# RPI-Lora-Gateway-Shield.net
KiCad netlist of a schematic drawn in EAGLE
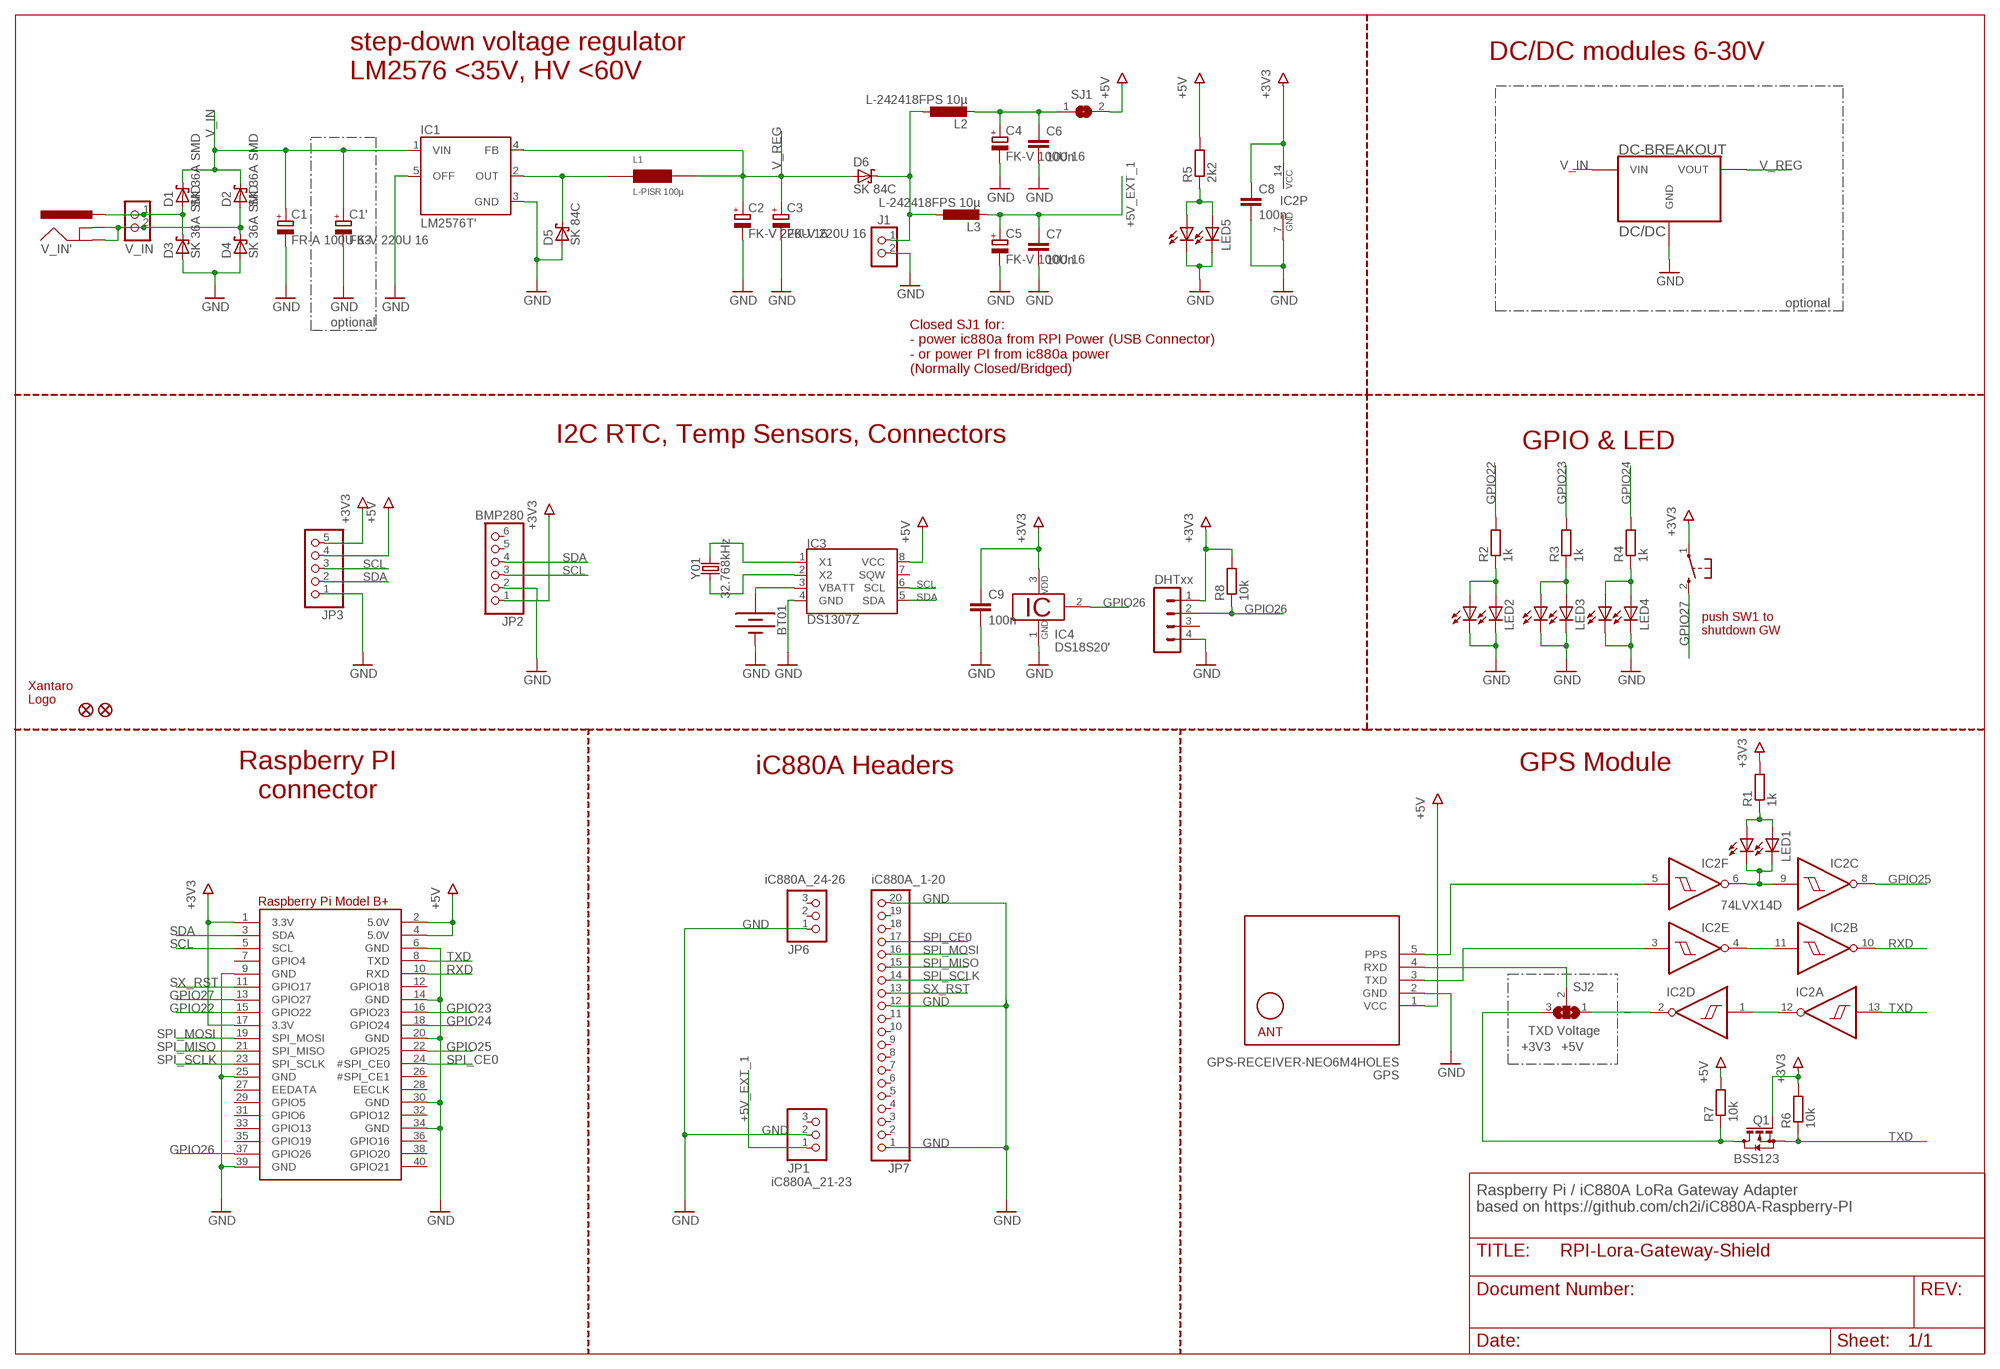
[diagram p0: schematic, sheet 1]

(export (version "E")
  (design (tool "Eeschema 10.0.6"))
  (components
    (comp (ref "BT01")
      (value "BATTERY-12MM_PTH")
      (footprint "eagle-import:BATTCON_12MM_PTH")
      (libsource (lib "eagle-import") (part "BATTERY-12MM_PTH"))
    )
    (comp (ref "C1")
      (value "FR-A 100U 63")
      (footprint "eagle-import:E3,5-8")
      (libsource (lib "eagle-import") (part "CPOL-EUE3.5-8"))
    )
    (comp (ref "C1'")
      (value "FK-V 220U 16")
      (footprint "eagle-import:PANASONIC_E")
      (libsource (lib "eagle-import") (part "CPOL-EUE"))
    )
    (comp (ref "C2")
      (value "FK-V 220U 16")
      (footprint "eagle-import:PANASONIC_E")
      (libsource (lib "eagle-import") (part "CPOL-EUE"))
    )
    (comp (ref "C3")
      (value "FK-V 220U 16")
      (footprint "eagle-import:PANASONIC_E")
      (libsource (lib "eagle-import") (part "CPOL-EUE"))
    )
    (comp (ref "C4")
      (value "FK-V 100U 16")
      (footprint "eagle-import:PANASONIC_D")
      (libsource (lib "eagle-import") (part "CPOL-EUD"))
    )
    (comp (ref "C5")
      (value "FK-V 100U 16")
      (footprint "eagle-import:PANASONIC_D")
      (libsource (lib "eagle-import") (part "CPOL-EUD"))
    )
    (comp (ref "C6")
      (value "100n")
      (footprint "eagle-import:C0805")
      (libsource (lib "eagle-import") (part "C-EUC0805"))
    )
    (comp (ref "C7")
      (value "100n")
      (footprint "eagle-import:C0805")
      (libsource (lib "eagle-import") (part "C-EUC0805"))
    )
    (comp (ref "C8")
      (value "100n")
      (footprint "eagle-import:C0805")
      (libsource (lib "eagle-import") (part "C-EUC0805"))
    )
    (comp (ref "C9")
      (value "100n")
      (footprint "eagle-import:C0805")
      (libsource (lib "eagle-import") (part "C-EUC0805"))
    )
    (comp (ref "D1")
      (value "SK 36A SMD")
      (footprint "eagle-import:SMB")
      (libsource (lib "eagle-import") (part "SCHOTTKY-DIODESMD"))
    )
    (comp (ref "D2")
      (value "SK 36A SMD")
      (footprint "eagle-import:SMB")
      (libsource (lib "eagle-import") (part "SCHOTTKY-DIODESMD"))
    )
    (comp (ref "D3")
      (value "SK 36A SMD")
      (footprint "eagle-import:SMB")
      (libsource (lib "eagle-import") (part "SCHOTTKY-DIODESMD"))
    )
    (comp (ref "D4")
      (value "SK 36A SMD")
      (footprint "eagle-import:SMB")
      (libsource (lib "eagle-import") (part "SCHOTTKY-DIODESMD"))
    )
    (comp (ref "D5")
      (value "SK 84C")
      (footprint "eagle-import:SMC")
      (libsource (lib "eagle-import") (part "SCHOTTKY-DIODESMC"))
    )
    (comp (ref "D6")
      (value "SK 84C")
      (footprint "eagle-import:SMC")
      (libsource (lib "eagle-import") (part "SCHOTTKY-DIODESMC"))
    )
    (comp (ref "DC/DC")
      (value "DC-BREAKOUT")
      (footprint "eagle-import:DC-BREAKOUT")
      (libsource (lib "eagle-import") (part "DC-BREAKOUTSTD"))
    )
    (comp (ref "FID2")
      (value "FIDUCIAL\"\"")
      (footprint "eagle-import:FIDUCIAL_1MM")
      (libsource (lib "eagle-import") (part "FIDUCIAL{dblquote}{dblquote}"))
    )
    (comp (ref "FID3")
      (value "FIDUCIAL\"\"")
      (footprint "eagle-import:FIDUCIAL_1MM")
      (libsource (lib "eagle-import") (part "FIDUCIAL{dblquote}{dblquote}"))
    )
    (comp (ref "GPS")
      (value "GPS-RECEIVER-NEO6M4HOLES")
      (footprint "eagle-import:GPS-RECEIVER-NEO6M_4HOLES")
      (libsource (lib "eagle-import") (part "GPS-RECEIVER-NEO6M4HOLES"))
    )
    (comp (ref "IC1")
      (value "LM2576T'")
      (footprint "eagle-import:TO220-5_90")
      (libsource (lib "eagle-import") (part "LM2576T'"))
    )
    (comp (ref "IC2")
      (value "74LVX14D")
      (footprint "eagle-import:SO14")
      (libsource (lib "eagle-import") (part "7414D"))
    )
    (comp (ref "IC3")
      (value "DS1307Z")
      (footprint "eagle-import:SO08-0.15")
      (libsource (lib "eagle-import") (part "DS1307Z"))
    )
    (comp (ref "IC4")
      (value "DS18S20'")
      (footprint "eagle-import:TO92-2")
      (libsource (lib "eagle-import") (part "DS18S20'"))
    )
    (comp (ref "J1")
      (value "+5V_IN")
      (footprint "eagle-import:TERMINAL_BLOCK_2P_5")
      (libsource (lib "eagle-import") (part "CON_TERMINAL_BLOCK_02-5MM"))
    )
    (comp (ref "J5")
      (value "DHTxx")
      (footprint "eagle-import:1X04_NO_LOCK")
      (libsource (lib "eagle-import") (part "CON_HEADER_1X04'NO_LOCK'"))
    )
    (comp (ref "JP1")
      (value "iC880A_21-23")
      (footprint "eagle-import:1X03")
      (libsource (lib "eagle-import") (part "PINHD-1X3"))
    )
    (comp (ref "JP2")
      (value "BMP280")
      (footprint "eagle-import:1X06")
      (libsource (lib "eagle-import") (part "PINHD-1X6"))
    )
    (comp (ref "JP3")
      (value "PINHD-1X5")
      (footprint "eagle-import:1X05")
      (libsource (lib "eagle-import") (part "PINHD-1X5"))
    )
    (comp (ref "JP6")
      (value "iC880A_24-26")
      (footprint "eagle-import:1X03")
      (libsource (lib "eagle-import") (part "PINHD-1X3"))
    )
    (comp (ref "JP7")
      (value "iC880A_1-20")
      (footprint "eagle-import:1X20")
      (libsource (lib "eagle-import") (part "PINHD-1X20"))
    )
    (comp (ref "L1")
      (value "L-PISR 100µ")
      (footprint "eagle-import:PISR")
      (libsource (lib "eagle-import") (part "PISR"))
    )
    (comp (ref "L2")
      (value "L-242418FPS 10µ")
      (footprint "eagle-import:L5650M")
      (libsource (lib "eagle-import") (part "L-EUL5650M"))
    )
    (comp (ref "L3")
      (value "L-242418FPS 10µ")
      (footprint "eagle-import:L5650M")
      (libsource (lib "eagle-import") (part "L-EUL5650M"))
    )
    (comp (ref "LED1")
      (value "LEDCHIPLED_0805")
      (footprint "eagle-import:CHIPLED_0805")
      (libsource (lib "eagle-import") (part "LEDCHIPLED_0805"))
    )
    (comp (ref "LED1'")
      (value "LED3MM")
      (footprint "eagle-import:LED3MM")
      (libsource (lib "eagle-import") (part "LED3MM"))
    )
    (comp (ref "LED2")
      (value "LEDCHIPLED_0805")
      (footprint "eagle-import:CHIPLED_0805")
      (libsource (lib "eagle-import") (part "LEDCHIPLED_0805"))
    )
    (comp (ref "LED2'")
      (value "LED3MM")
      (footprint "eagle-import:LED3MM")
      (libsource (lib "eagle-import") (part "LED3MM"))
    )
    (comp (ref "LED3")
      (value "LEDCHIPLED_0805")
      (footprint "eagle-import:CHIPLED_0805")
      (libsource (lib "eagle-import") (part "LEDCHIPLED_0805"))
    )
    (comp (ref "LED3'")
      (value "LED3MM")
      (footprint "eagle-import:LED3MM")
      (libsource (lib "eagle-import") (part "LED3MM"))
    )
    (comp (ref "LED4")
      (value "LEDCHIPLED_0805")
      (footprint "eagle-import:CHIPLED_0805")
      (libsource (lib "eagle-import") (part "LEDCHIPLED_0805"))
    )
    (comp (ref "LED4'")
      (value "LED3MM")
      (footprint "eagle-import:LED3MM")
      (libsource (lib "eagle-import") (part "LED3MM"))
    )
    (comp (ref "LED5")
      (value "LEDCHIPLED_0805")
      (footprint "eagle-import:CHIPLED_0805")
      (libsource (lib "eagle-import") (part "LEDCHIPLED_0805"))
    )
    (comp (ref "LED5'")
      (value "LED3MM")
      (footprint "eagle-import:LED3MM")
      (libsource (lib "eagle-import") (part "LED3MM"))
    )
    (comp (ref "Q1")
      (value "BSS123")
      (footprint "eagle-import:SOT23")
      (libsource (lib "eagle-import") (part "BSS123"))
    )
    (comp (ref "R1")
      (value "1k")
      (footprint "eagle-import:R0805")
      (libsource (lib "eagle-import") (part "R-EU_R0805"))
    )
    (comp (ref "R2")
      (value "1k")
      (footprint "eagle-import:R0805")
      (libsource (lib "eagle-import") (part "R-EU_R0805"))
    )
    (comp (ref "R3")
      (value "1k")
      (footprint "eagle-import:R0805")
      (libsource (lib "eagle-import") (part "R-EU_R0805"))
    )
    (comp (ref "R4")
      (value "1k")
      (footprint "eagle-import:R0805")
      (libsource (lib "eagle-import") (part "R-EU_R0805"))
    )
    (comp (ref "R5")
      (value "2k2")
      (footprint "eagle-import:R0805")
      (libsource (lib "eagle-import") (part "R-EU_R0805"))
    )
    (comp (ref "R6")
      (value "10k")
      (footprint "eagle-import:R0805")
      (libsource (lib "eagle-import") (part "R-EU_R0805"))
    )
    (comp (ref "R7")
      (value "10k")
      (footprint "eagle-import:R0805")
      (libsource (lib "eagle-import") (part "R-EU_R0805"))
    )
    (comp (ref "R8")
      (value "10k")
      (footprint "eagle-import:R0805")
      (libsource (lib "eagle-import") (part "R-EU_R0805"))
    )
    (comp (ref "RPI1")
      (value "RASPBERRYPI_BPLUS_IDC")
      (footprint "eagle-import:2X20")
      (libsource (lib "eagle-import") (part "RASPBERRYPI_BPLUS_IDC"))
    )
    (comp (ref "SJ1")
      (value "SJCLOSED")
      (footprint "eagle-import:SJ_CLOSED")
      (libsource (lib "eagle-import") (part "SJCLOSED"))
    )
    (comp (ref "SJ2")
      (value "TXD Voltage")
      (footprint "eagle-import:SJ_2")
      (libsource (lib "eagle-import") (part "SJ2W"))
    )
    (comp (ref "SW1'")
      (value "RESET")
      (footprint "eagle-import:KSS-2EG4430")
      (libsource (lib "eagle-import") (part "KSS-2EG4430"))
    )
    (comp (ref "U$4")
      (value "XAN_LOGO_FULL_SILK_L")
      (footprint "eagle-import:XAN_FULL_SILK_L")
      (libsource (lib "eagle-import") (part "XAN_LOGO_FULL_SILK_L"))
    )
    (comp (ref "V_IN")
      (value "V_IN")
      (footprint "eagle-import:TERMINAL_BLOCK_2P_5")
      (libsource (lib "eagle-import") (part "CON_TERMINAL_BLOCK_02-5MM"))
    )
    (comp (ref "V_IN'")
      (value "POWER_JACKPTH")
      (footprint "eagle-import:POWER_JACK_PTH")
      (libsource (lib "eagle-import") (part "POWER_JACKPTH"))
    )
    (comp (ref "Y01")
      (value "32.768kHz")
      (footprint "eagle-import:CRYSTAL-SMD-2X6-CYL")
      (libsource (lib "eagle-import") (part "CRYSTAL-32.768KHZSMD-2X6"))
    )
  )
  (nets
    (net (code "1") (name "+3V3") (class "Default")
      (node (ref "C8") (pin "1") (pinfunction "1_1") (pintype "passive"))
      (node (ref "C9") (pin "1") (pinfunction "1_1") (pintype "passive"))
      (node (ref "IC2") (pin "14") (pinfunction "VCC_14") (pintype "power_in"))
      (node (ref "IC4") (pin "3") (pinfunction "VDD_3") (pintype "power_in"))
      (node (ref "J5") (pin "1") (pinfunction "1_1") (pintype "passive"))
      (node (ref "JP2") (pin "1") (pinfunction "1_1") (pintype "passive"))
      (node (ref "JP3") (pin "5") (pinfunction "5_5") (pintype "passive"))
      (node (ref "Q1") (pin "1") (pinfunction "G_1") (pintype "passive"))
      (node (ref "R1") (pin "2") (pinfunction "2_2") (pintype "passive"))
      (node (ref "R6") (pin "2") (pinfunction "2_2") (pintype "passive"))
      (node (ref "R8") (pin "2") (pinfunction "2_2") (pintype "passive"))
      (node (ref "RPI1") (pin "1") (pinfunction "3.3V_1") (pintype "power_in"))
      (node (ref "RPI1") (pin "17") (pinfunction "3.3V_17") (pintype "power_in"))
      (node (ref "SW1'") (pin "1") (pinfunction "P_1") (pintype "passive"))
    )
    (net (code "2") (name "+5V") (class "Default")
      (node (ref "GPS") (pin "1") (pinfunction "VCC_1") (pintype "bidirectional"))
      (node (ref "IC3") (pin "8") (pinfunction "VCC_8") (pintype "bidirectional"))
      (node (ref "JP3") (pin "4") (pinfunction "4_4") (pintype "passive"))
      (node (ref "R5") (pin "2") (pinfunction "2_2") (pintype "passive"))
      (node (ref "R7") (pin "2") (pinfunction "2_2") (pintype "passive"))
      (node (ref "RPI1") (pin "2") (pinfunction "5.0V_2") (pintype "power_in"))
      (node (ref "RPI1") (pin "4") (pinfunction "5.0V_4") (pintype "power_in"))
      (node (ref "SJ1") (pin "2") (pinfunction "2_2") (pintype "passive"))
    )
    (net (code "3") (name "/+5V_EXT_1") (class "Default")
      (node (ref "C5") (pin "+") (pinfunction "+_+") (pintype "passive"))
      (node (ref "C7") (pin "1") (pinfunction "1_1") (pintype "passive"))
      (node (ref "JP1") (pin "1") (pinfunction "1_1") (pintype "passive"))
      (node (ref "L3") (pin "2") (pinfunction "2_2") (pintype "passive"))
    )
    (net (code "4") (name "/EECLK") (class "Default")
      (node (ref "RPI1") (pin "28") (pinfunction "EECLK_28") (pintype "power_in"))
    )
    (net (code "5") (name "/GPIO6") (class "Default")
      (node (ref "RPI1") (pin "31") (pinfunction "GPIO6_31") (pintype "power_in"))
    )
    (net (code "6") (name "/GPIO16") (class "Default")
      (node (ref "RPI1") (pin "36") (pinfunction "GPIO16_36") (pintype "power_in"))
    )
    (net (code "7") (name "/GPIO22") (class "Default")
      (node (ref "R2") (pin "2") (pinfunction "2_2") (pintype "passive"))
      (node (ref "RPI1") (pin "15") (pinfunction "GPIO22_15") (pintype "bidirectional"))
    )
    (net (code "8") (name "/GPIO23") (class "Default")
      (node (ref "R3") (pin "2") (pinfunction "2_2") (pintype "passive"))
      (node (ref "RPI1") (pin "16") (pinfunction "GPIO23_16") (pintype "bidirectional"))
    )
    (net (code "9") (name "/GPIO24") (class "Default")
      (node (ref "R4") (pin "2") (pinfunction "2_2") (pintype "passive"))
      (node (ref "RPI1") (pin "18") (pinfunction "GPIO24_18") (pintype "bidirectional"))
    )
    (net (code "10") (name "/GPIO25") (class "Default")
      (node (ref "IC2") (pin "8") (pinfunction "O_8") (pintype "output"))
      (node (ref "RPI1") (pin "22") (pinfunction "GPIO25_22") (pintype "bidirectional"))
    )
    (net (code "11") (name "/GPIO26") (class "Default")
      (node (ref "IC4") (pin "2") (pinfunction "1W_2") (pintype "power_in"))
      (node (ref "J5") (pin "2") (pinfunction "2_2") (pintype "passive"))
      (node (ref "R8") (pin "1") (pinfunction "1_1") (pintype "passive"))
      (node (ref "RPI1") (pin "37") (pinfunction "GPIO26_37") (pintype "bidirectional"))
    )
    (net (code "12") (name "/GPIO27") (class "Default")
      (node (ref "RPI1") (pin "13") (pinfunction "GPIO27_13") (pintype "bidirectional"))
      (node (ref "SW1'") (pin "2") (pinfunction "S_2") (pintype "passive"))
    )
    (net (code "13") (name "/RXD") (class "Default")
      (node (ref "IC2") (pin "10") (pinfunction "O_10") (pintype "output"))
      (node (ref "RPI1") (pin "10") (pinfunction "RXD_10") (pintype "bidirectional"))
    )
    (net (code "14") (name "/SCL") (class "Default")
      (node (ref "IC3") (pin "6") (pinfunction "SCL_6") (pintype "bidirectional"))
      (node (ref "JP2") (pin "3") (pinfunction "3_3") (pintype "passive"))
      (node (ref "JP3") (pin "3") (pinfunction "3_3") (pintype "passive"))
      (node (ref "RPI1") (pin "5") (pinfunction "SCL_5") (pintype "bidirectional"))
    )
    (net (code "15") (name "/SDA") (class "Default")
      (node (ref "IC3") (pin "5") (pinfunction "SDA_5") (pintype "bidirectional"))
      (node (ref "JP2") (pin "4") (pinfunction "4_4") (pintype "passive"))
      (node (ref "JP3") (pin "2") (pinfunction "2_2") (pintype "passive"))
      (node (ref "RPI1") (pin "3") (pinfunction "SDA_3") (pintype "bidirectional"))
    )
    (net (code "16") (name "/SPI_CE0") (class "Default")
      (node (ref "JP7") (pin "17") (pinfunction "17_17") (pintype "passive"))
      (node (ref "RPI1") (pin "24") (pinfunction "#SPI_CE0_24") (pintype "bidirectional"))
    )
    (net (code "17") (name "/SPI_MISO") (class "Default")
      (node (ref "JP7") (pin "15") (pinfunction "15_15") (pintype "passive"))
      (node (ref "RPI1") (pin "21") (pinfunction "SPI_MISO_21") (pintype "bidirectional"))
    )
    (net (code "18") (name "/SPI_MOSI") (class "Default")
      (node (ref "JP7") (pin "16") (pinfunction "16_16") (pintype "passive"))
      (node (ref "RPI1") (pin "19") (pinfunction "SPI_MOSI_19") (pintype "bidirectional"))
    )
    (net (code "19") (name "/SPI_SCLK") (class "Default")
      (node (ref "JP7") (pin "14") (pinfunction "14_14") (pintype "passive"))
      (node (ref "RPI1") (pin "23") (pinfunction "SPI_SCLK_23") (pintype "bidirectional"))
    )
    (net (code "20") (name "/SX_RST") (class "Default")
      (node (ref "JP7") (pin "13") (pinfunction "13_13") (pintype "passive"))
      (node (ref "RPI1") (pin "11") (pinfunction "GPIO17_11") (pintype "bidirectional"))
    )
    (net (code "21") (name "/TXD") (class "Default")
      (node (ref "IC2") (pin "13") (pinfunction "I_13") (pintype "input"))
      (node (ref "Q1") (pin "2") (pinfunction "S_2") (pintype "passive"))
      (node (ref "R6") (pin "1") (pinfunction "1_1") (pintype "passive"))
      (node (ref "RPI1") (pin "8") (pinfunction "TXD_8") (pintype "output"))
    )
    (net (code "22") (name "/V_IN") (class "Default")
      (node (ref "C1") (pin "+") (pinfunction "+_+") (pintype "passive"))
      (node (ref "C1'") (pin "+") (pinfunction "+_+") (pintype "passive"))
      (node (ref "D1") (pin "C") (pinfunction "C_C") (pintype "passive"))
      (node (ref "D2") (pin "C") (pinfunction "C_C") (pintype "passive"))
      (node (ref "DC/DC") (pin "VIN-1") (pinfunction "VIN_VIN-1") (pintype "input"))
      (node (ref "DC/DC") (pin "VIN-2") (pinfunction "VIN_VIN-2") (pintype "input"))
      (node (ref "IC1") (pin "1") (pinfunction "VIN_1") (pintype "power_in"))
    )
    (net (code "23") (name "/V_REG") (class "Default")
      (node (ref "C2") (pin "+") (pinfunction "+_+") (pintype "passive"))
      (node (ref "C3") (pin "+") (pinfunction "+_+") (pintype "passive"))
      (node (ref "D6") (pin "A") (pinfunction "A_A") (pintype "passive"))
      (node (ref "DC/DC") (pin "VOUT-1") (pinfunction "VOUT_VOUT-1") (pintype "output"))
      (node (ref "DC/DC") (pin "VOUT-2") (pinfunction "VOUT_VOUT-2") (pintype "output"))
      (node (ref "IC1") (pin "4") (pinfunction "FB_4") (pintype "input"))
      (node (ref "L1") (pin "2") (pinfunction "P$2_2") (pintype "bidirectional"))
    )
    (net (code "24") (name "GND") (class "Default")
      (node (ref "BT01") (pin "2") (pinfunction "-_2") (pintype "power_in"))
      (node (ref "C1") (pin "-") (pinfunction "-_-") (pintype "passive"))
      (node (ref "C1'") (pin "-") (pinfunction "-_-") (pintype "passive"))
      (node (ref "C2") (pin "-") (pinfunction "-_-") (pintype "passive"))
      (node (ref "C3") (pin "-") (pinfunction "-_-") (pintype "passive"))
      (node (ref "C4") (pin "-") (pinfunction "-_-") (pintype "passive"))
      (node (ref "C5") (pin "-") (pinfunction "-_-") (pintype "passive"))
      (node (ref "C6") (pin "2") (pinfunction "2_2") (pintype "passive"))
      (node (ref "C7") (pin "2") (pinfunction "2_2") (pintype "passive"))
      (node (ref "C8") (pin "2") (pinfunction "2_2") (pintype "passive"))
      (node (ref "C9") (pin "2") (pinfunction "2_2") (pintype "passive"))
      (node (ref "D3") (pin "A") (pinfunction "A_A") (pintype "passive"))
      (node (ref "D4") (pin "A") (pinfunction "A_A") (pintype "passive"))
      (node (ref "D5") (pin "A") (pinfunction "A_A") (pintype "passive"))
      (node (ref "DC/DC") (pin "GND-1") (pinfunction "GND_GND-1") (pintype "passive"))
      (node (ref "DC/DC") (pin "GND-2") (pinfunction "GND_GND-2") (pintype "passive"))
      (node (ref "DC/DC") (pin "GND-3") (pinfunction "GND_GND-3") (pintype "passive"))
      (node (ref "DC/DC") (pin "GND-4") (pinfunction "GND_GND-4") (pintype "passive"))
      (node (ref "GPS") (pin "2") (pinfunction "GND_2") (pintype "bidirectional"))
      (node (ref "IC1") (pin "3") (pinfunction "GND_3") (pintype "power_in"))
      (node (ref "IC1") (pin "5") (pinfunction "OFF_5") (pintype "input"))
      (node (ref "IC2") (pin "7") (pinfunction "GND_7") (pintype "power_in"))
      (node (ref "IC3") (pin "4") (pinfunction "GND_4") (pintype "bidirectional"))
      (node (ref "IC4") (pin "1") (pinfunction "GND_1") (pintype "power_in"))
      (node (ref "J1") (pin "2") (pinfunction "2_2") (pintype "passive"))
      (node (ref "J5") (pin "4") (pinfunction "4_4") (pintype "passive"))
      (node (ref "JP1") (pin "2") (pinfunction "2_2") (pintype "passive"))
      (node (ref "JP2") (pin "2") (pinfunction "2_2") (pintype "passive"))
      (node (ref "JP3") (pin "1") (pinfunction "1_1") (pintype "passive"))
      (node (ref "JP6") (pin "1") (pinfunction "1_1") (pintype "passive"))
      (node (ref "JP7") (pin "1") (pinfunction "1_1") (pintype "passive"))
      (node (ref "JP7") (pin "12") (pinfunction "12_12") (pintype "passive"))
      (node (ref "JP7") (pin "20") (pinfunction "20_20") (pintype "passive"))
      (node (ref "LED2") (pin "C") (pinfunction "C_C") (pintype "passive"))
      (node (ref "LED2'") (pin "K") (pinfunction "C_K") (pintype "passive"))
      (node (ref "LED3") (pin "C") (pinfunction "C_C") (pintype "passive"))
      (node (ref "LED3'") (pin "K") (pinfunction "C_K") (pintype "passive"))
      (node (ref "LED4") (pin "C") (pinfunction "C_C") (pintype "passive"))
      (node (ref "LED4'") (pin "K") (pinfunction "C_K") (pintype "passive"))
      (node (ref "LED5") (pin "C") (pinfunction "C_C") (pintype "passive"))
      (node (ref "LED5'") (pin "K") (pinfunction "C_K") (pintype "passive"))
      (node (ref "RPI1") (pin "14") (pinfunction "GND_14") (pintype "power_in"))
      (node (ref "RPI1") (pin "20") (pinfunction "GND_20") (pintype "power_in"))
      (node (ref "RPI1") (pin "25") (pinfunction "GND_25") (pintype "power_in"))
      (node (ref "RPI1") (pin "30") (pinfunction "GND_30") (pintype "bidirectional"))
      (node (ref "RPI1") (pin "34") (pinfunction "GND_34") (pintype "bidirectional"))
      (node (ref "RPI1") (pin "39") (pinfunction "GND_39") (pintype "power_in"))
      (node (ref "RPI1") (pin "6") (pinfunction "GND_6") (pintype "power_in"))
      (node (ref "RPI1") (pin "9") (pinfunction "GND_9") (pintype "power_in"))
    )
    (net (code "25") (name "Net-(BT01-+)") (class "Default")
      (node (ref "BT01") (pin "1") (pinfunction "+_1") (pintype "power_in"))
      (node (ref "IC3") (pin "3") (pinfunction "VBATT_3") (pintype "bidirectional"))
    )
    (net (code "26") (name "Net-(C4-Pad+)") (class "Default")
      (node (ref "C4") (pin "+") (pinfunction "+_+") (pintype "passive"))
      (node (ref "C6") (pin "1") (pinfunction "1_1") (pintype "passive"))
      (node (ref "L2") (pin "2") (pinfunction "2_2") (pintype "passive"))
      (node (ref "SJ1") (pin "1") (pinfunction "1_1") (pintype "passive"))
    )
    (net (code "27") (name "Net-(D1-PadA)") (class "Default")
      (node (ref "D1") (pin "A") (pinfunction "A_A") (pintype "passive"))
      (node (ref "D3") (pin "C") (pinfunction "C_C") (pintype "passive"))
      (node (ref "V_IN") (pin "1") (pinfunction "1_1") (pintype "passive"))
      (node (ref "V_IN'") (pin "PWR") (pinfunction "PWR_PWR") (pintype "bidirectional"))
    )
    (net (code "28") (name "Net-(D2-PadA)") (class "Default")
      (node (ref "D2") (pin "A") (pinfunction "A_A") (pintype "passive"))
      (node (ref "D4") (pin "C") (pinfunction "C_C") (pintype "passive"))
      (node (ref "V_IN") (pin "2") (pinfunction "2_2") (pintype "passive"))
      (node (ref "V_IN'") (pin "GND") (pinfunction "GND_GND") (pintype "bidirectional"))
      (node (ref "V_IN'") (pin "GNDBREAK") (pinfunction "GNDBREAK_GNDBREAK") (pintype "bidirectional"))
    )
    (net (code "29") (name "Net-(D6-PadC)") (class "Default")
      (node (ref "D6") (pin "C") (pinfunction "C_C") (pintype "passive"))
      (node (ref "J1") (pin "1") (pinfunction "1_1") (pintype "passive"))
      (node (ref "L2") (pin "1") (pinfunction "1_1") (pintype "passive"))
      (node (ref "L3") (pin "1") (pinfunction "1_1") (pintype "passive"))
    )
    (net (code "30") (name "Net-(GPS-PPS)") (class "Default")
      (node (ref "GPS") (pin "5") (pinfunction "PPS_5") (pintype "power_in"))
      (node (ref "IC2") (pin "5") (pinfunction "I_5") (pintype "input"))
    )
    (net (code "31") (name "Net-(GPS-RXD)") (class "Default")
      (node (ref "GPS") (pin "4") (pinfunction "RXD_4") (pintype "power_in"))
      (node (ref "SJ2") (pin "2") (pinfunction "2_2") (pintype "passive"))
    )
    (net (code "32") (name "Net-(GPS-TXD)") (class "Default")
      (node (ref "GPS") (pin "3") (pinfunction "TXD_3") (pintype "bidirectional"))
      (node (ref "IC2") (pin "3") (pinfunction "I_3") (pintype "input"))
    )
    (net (code "33") (name "Net-(IC1-OUT)") (class "Default")
      (node (ref "D5") (pin "C") (pinfunction "C_C") (pintype "passive"))
      (node (ref "IC1") (pin "2") (pinfunction "OUT_2") (pintype "output"))
      (node (ref "L1") (pin "1") (pinfunction "P$1_1") (pintype "bidirectional"))
    )
    (net (code "34") (name "Net-(IC2A-O)") (class "Default")
      (node (ref "IC2") (pin "1") (pinfunction "I_1") (pintype "input"))
      (node (ref "IC2") (pin "12") (pinfunction "O_12") (pintype "output"))
    )
    (net (code "35") (name "Net-(IC2B-I)") (class "Default")
      (node (ref "IC2") (pin "11") (pinfunction "I_11") (pintype "input"))
      (node (ref "IC2") (pin "4") (pinfunction "O_4") (pintype "output"))
    )
    (net (code "36") (name "Net-(IC2C-I)") (class "Default")
      (node (ref "IC2") (pin "6") (pinfunction "O_6") (pintype "output"))
      (node (ref "IC2") (pin "9") (pinfunction "I_9") (pintype "input"))
      (node (ref "LED1") (pin "C") (pinfunction "C_C") (pintype "passive"))
      (node (ref "LED1'") (pin "K") (pinfunction "C_K") (pintype "passive"))
    )
    (net (code "37") (name "Net-(IC2D-O)") (class "Default")
      (node (ref "IC2") (pin "2") (pinfunction "O_2") (pintype "output"))
      (node (ref "SJ2") (pin "1") (pinfunction "1_1") (pintype "passive"))
    )
    (net (code "38") (name "Net-(IC3-X1)") (class "Default")
      (node (ref "IC3") (pin "1") (pinfunction "X1_1") (pintype "bidirectional"))
      (node (ref "Y01") (pin "X2") (pinfunction "2_X2") (pintype "passive"))
    )
    (net (code "39") (name "Net-(IC3-X2)") (class "Default")
      (node (ref "IC3") (pin "2") (pinfunction "X2_2") (pintype "bidirectional"))
      (node (ref "Y01") (pin "X1") (pinfunction "1_X1") (pintype "passive"))
    )
    (net (code "40") (name "Net-(LED1'-PadA)") (class "Default")
      (node (ref "LED1") (pin "A") (pinfunction "A_A") (pintype "passive"))
      (node (ref "LED1'") (pin "A") (pinfunction "A_A") (pintype "passive"))
      (node (ref "R1") (pin "1") (pinfunction "1_1") (pintype "passive"))
    )
    (net (code "41") (name "Net-(LED2'-PadA)") (class "Default")
      (node (ref "LED2") (pin "A") (pinfunction "A_A") (pintype "passive"))
      (node (ref "LED2'") (pin "A") (pinfunction "A_A") (pintype "passive"))
      (node (ref "R2") (pin "1") (pinfunction "1_1") (pintype "passive"))
    )
    (net (code "42") (name "Net-(LED3'-PadA)") (class "Default")
      (node (ref "LED3") (pin "A") (pinfunction "A_A") (pintype "passive"))
      (node (ref "LED3'") (pin "A") (pinfunction "A_A") (pintype "passive"))
      (node (ref "R3") (pin "1") (pinfunction "1_1") (pintype "passive"))
    )
    (net (code "43") (name "Net-(LED4'-PadA)") (class "Default")
      (node (ref "LED4") (pin "A") (pinfunction "A_A") (pintype "passive"))
      (node (ref "LED4'") (pin "A") (pinfunction "A_A") (pintype "passive"))
      (node (ref "R4") (pin "1") (pinfunction "1_1") (pintype "passive"))
    )
    (net (code "44") (name "Net-(LED5'-PadA)") (class "Default")
      (node (ref "LED5") (pin "A") (pinfunction "A_A") (pintype "passive"))
      (node (ref "LED5'") (pin "A") (pinfunction "A_A") (pintype "passive"))
      (node (ref "R5") (pin "1") (pinfunction "1_1") (pintype "passive"))
    )
    (net (code "45") (name "Net-(Q1-D)") (class "Default")
      (node (ref "Q1") (pin "3") (pinfunction "D_3") (pintype "passive"))
      (node (ref "R7") (pin "1") (pinfunction "1_1") (pintype "passive"))
      (node (ref "SJ2") (pin "3") (pinfunction "3_3") (pintype "passive"))
    )
    (net (code "46") (name "unconnected-(IC3-SQW-Pad7)") (class "Default")
      (node (ref "IC3") (pin "7") (pinfunction "SQW_7") (pintype "bidirectional"))
    )
    (net (code "47") (name "unconnected-(J5-Pad3)") (class "Default")
      (node (ref "J5") (pin "3") (pinfunction "3_3") (pintype "passive"))
    )
    (net (code "48") (name "unconnected-(JP1-Pad3)") (class "Default")
      (node (ref "JP1") (pin "3") (pinfunction "3_3") (pintype "passive"))
    )
    (net (code "49") (name "unconnected-(JP2-Pad5)") (class "Default")
      (node (ref "JP2") (pin "5") (pinfunction "5_5") (pintype "passive"))
    )
    (net (code "50") (name "unconnected-(JP2-Pad6)") (class "Default")
      (node (ref "JP2") (pin "6") (pinfunction "6_6") (pintype "passive"))
    )
    (net (code "51") (name "unconnected-(JP6-Pad2)") (class "Default")
      (node (ref "JP6") (pin "2") (pinfunction "2_2") (pintype "passive"))
    )
    (net (code "52") (name "unconnected-(JP6-Pad3)") (class "Default")
      (node (ref "JP6") (pin "3") (pinfunction "3_3") (pintype "passive"))
    )
    (net (code "53") (name "unconnected-(JP7-Pad2)") (class "Default")
      (node (ref "JP7") (pin "2") (pinfunction "2_2") (pintype "passive"))
    )
    (net (code "54") (name "unconnected-(JP7-Pad3)") (class "Default")
      (node (ref "JP7") (pin "3") (pinfunction "3_3") (pintype "passive"))
    )
    (net (code "55") (name "unconnected-(JP7-Pad4)") (class "Default")
      (node (ref "JP7") (pin "4") (pinfunction "4_4") (pintype "passive"))
    )
    (net (code "56") (name "unconnected-(JP7-Pad5)") (class "Default")
      (node (ref "JP7") (pin "5") (pinfunction "5_5") (pintype "passive"))
    )
    (net (code "57") (name "unconnected-(JP7-Pad6)") (class "Default")
      (node (ref "JP7") (pin "6") (pinfunction "6_6") (pintype "passive"))
    )
    (net (code "58") (name "unconnected-(JP7-Pad7)") (class "Default")
      (node (ref "JP7") (pin "7") (pinfunction "7_7") (pintype "passive"))
    )
    (net (code "59") (name "unconnected-(JP7-Pad8)") (class "Default")
      (node (ref "JP7") (pin "8") (pinfunction "8_8") (pintype "passive"))
    )
    (net (code "60") (name "unconnected-(JP7-Pad9)") (class "Default")
      (node (ref "JP7") (pin "9") (pinfunction "9_9") (pintype "passive"))
    )
    (net (code "61") (name "unconnected-(JP7-Pad10)") (class "Default")
      (node (ref "JP7") (pin "10") (pinfunction "10_10") (pintype "passive"))
    )
    (net (code "62") (name "unconnected-(JP7-Pad11)") (class "Default")
      (node (ref "JP7") (pin "11") (pinfunction "11_11") (pintype "passive"))
    )
    (net (code "63") (name "unconnected-(JP7-Pad18)") (class "Default")
      (node (ref "JP7") (pin "18") (pinfunction "18_18") (pintype "passive"))
    )
    (net (code "64") (name "unconnected-(JP7-Pad19)") (class "Default")
      (node (ref "JP7") (pin "19") (pinfunction "19_19") (pintype "passive"))
    )
    (net (code "65") (name "unconnected-(RPI1-#SPI_CE1-Pad26)") (class "Default")
      (node (ref "RPI1") (pin "26") (pinfunction "#SPI_CE1_26") (pintype "bidirectional"))
    )
    (net (code "66") (name "unconnected-(RPI1-EEDATA-Pad27)") (class "Default")
      (node (ref "RPI1") (pin "27") (pinfunction "EEDATA_27") (pintype "bidirectional"))
    )
    (net (code "67") (name "unconnected-(RPI1-GPIO4-Pad7)") (class "Default")
      (node (ref "RPI1") (pin "7") (pinfunction "GPIO4_7") (pintype "bidirectional"))
    )
    (net (code "68") (name "unconnected-(RPI1-GPIO5-Pad29)") (class "Default")
      (node (ref "RPI1") (pin "29") (pinfunction "GPIO5_29") (pintype "bidirectional"))
    )
    (net (code "69") (name "unconnected-(RPI1-GPIO12-Pad32)") (class "Default")
      (node (ref "RPI1") (pin "32") (pinfunction "GPIO12_32") (pintype "bidirectional"))
    )
    (net (code "70") (name "unconnected-(RPI1-GPIO13-Pad33)") (class "Default")
      (node (ref "RPI1") (pin "33") (pinfunction "GPIO13_33") (pintype "bidirectional"))
    )
    (net (code "71") (name "unconnected-(RPI1-GPIO18-Pad12)") (class "Default")
      (node (ref "RPI1") (pin "12") (pinfunction "GPIO18_12") (pintype "bidirectional"))
    )
    (net (code "72") (name "unconnected-(RPI1-GPIO19-Pad35)") (class "Default")
      (node (ref "RPI1") (pin "35") (pinfunction "GPIO19_35") (pintype "bidirectional"))
    )
    (net (code "73") (name "unconnected-(RPI1-GPIO20-Pad38)") (class "Default")
      (node (ref "RPI1") (pin "38") (pinfunction "GPIO20_38") (pintype "bidirectional"))
    )
    (net (code "74") (name "unconnected-(RPI1-GPIO21-Pad40)") (class "Default")
      (node (ref "RPI1") (pin "40") (pinfunction "GPIO21_40") (pintype "bidirectional"))
    )
  )
)
